# switch.net
KiCad netlist of a schematic drawn in EAGLE
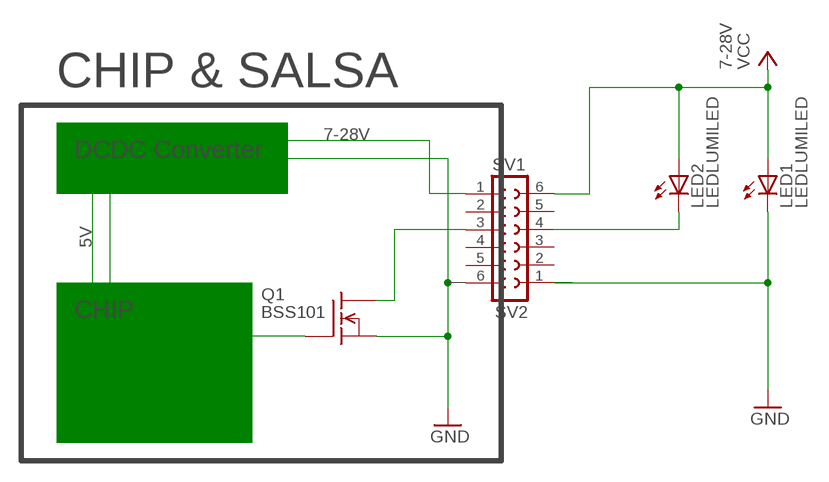
[diagram p0: schematic, sheet 1]

(export (version "E")
  (design (tool "Eeschema 10.0.6"))
  (components
    (comp (ref "LED1")
      (value "LEDLUMILED")
      (footprint "eagle-import:LUMILED")
      (libsource (lib "eagle-import") (part "LEDLUMILED"))
    )
    (comp (ref "LED2")
      (value "LEDLUMILED")
      (footprint "eagle-import:LUMILED")
      (libsource (lib "eagle-import") (part "LEDLUMILED"))
    )
    (comp (ref "Q1")
      (value "BSS101")
      (footprint "eagle-import:TO92")
      (libsource (lib "eagle-import") (part "BSS101"))
    )
    (comp (ref "SV1")
      (value "FE06-1")
      (footprint "eagle-import:FE06")
      (libsource (lib "eagle-import") (part "FE06-1"))
    )
    (comp (ref "SV2")
      (value "FE06-1")
      (footprint "eagle-import:FE06")
      (libsource (lib "eagle-import") (part "FE06-1"))
    )
  )
  (nets
    (net (code "1") (name "GND") (class "Default")
      (node (ref "LED1") (pin "4-") (pinfunction "C_4-") (pintype "passive"))
      (node (ref "Q1") (pin "1") (pinfunction "S_1") (pintype "passive"))
      (node (ref "SV1") (pin "1") (pinfunction "1_1") (pintype "passive"))
      (node (ref "SV2") (pin "6") (pinfunction "6_6") (pintype "passive"))
    )
    (net (code "2") (name "Net-(LED2-C)") (class "Default")
      (node (ref "LED2") (pin "4-") (pinfunction "C_4-") (pintype "passive"))
      (node (ref "SV1") (pin "4") (pinfunction "4_4") (pintype "passive"))
    )
    (net (code "3") (name "Net-(Q1-D)") (class "Default")
      (node (ref "Q1") (pin "3") (pinfunction "D_3") (pintype "passive"))
      (node (ref "SV2") (pin "3") (pinfunction "3_3") (pintype "passive"))
    )
    (net (code "4") (name "VCC") (class "Default")
      (node (ref "LED1") (pin "2+") (pinfunction "A_2+") (pintype "passive"))
      (node (ref "LED2") (pin "2+") (pinfunction "A_2+") (pintype "passive"))
      (node (ref "SV1") (pin "6") (pinfunction "6_6") (pintype "passive"))
    )
    (net (code "5") (name "unconnected-(Q1-G-Pad2)") (class "Default")
      (node (ref "Q1") (pin "2") (pinfunction "G_2") (pintype "passive"))
    )
    (net (code "6") (name "unconnected-(SV1-Pad2)") (class "Default")
      (node (ref "SV1") (pin "2") (pinfunction "2_2") (pintype "passive"))
    )
    (net (code "7") (name "unconnected-(SV1-Pad3)") (class "Default")
      (node (ref "SV1") (pin "3") (pinfunction "3_3") (pintype "passive"))
    )
    (net (code "8") (name "unconnected-(SV1-Pad5)") (class "Default")
      (node (ref "SV1") (pin "5") (pinfunction "5_5") (pintype "passive"))
    )
    (net (code "9") (name "unconnected-(SV2-Pad1)") (class "Default")
      (node (ref "SV2") (pin "1") (pinfunction "1_1") (pintype "passive"))
    )
    (net (code "10") (name "unconnected-(SV2-Pad2)") (class "Default")
      (node (ref "SV2") (pin "2") (pinfunction "2_2") (pintype "passive"))
    )
    (net (code "11") (name "unconnected-(SV2-Pad4)") (class "Default")
      (node (ref "SV2") (pin "4") (pinfunction "4_4") (pintype "passive"))
    )
    (net (code "12") (name "unconnected-(SV2-Pad5)") (class "Default")
      (node (ref "SV2") (pin "5") (pinfunction "5_5") (pintype "passive"))
    )
  )
)
